# 411_AutoFan_1.net
KiCad netlist of a schematic drawn in EAGLE
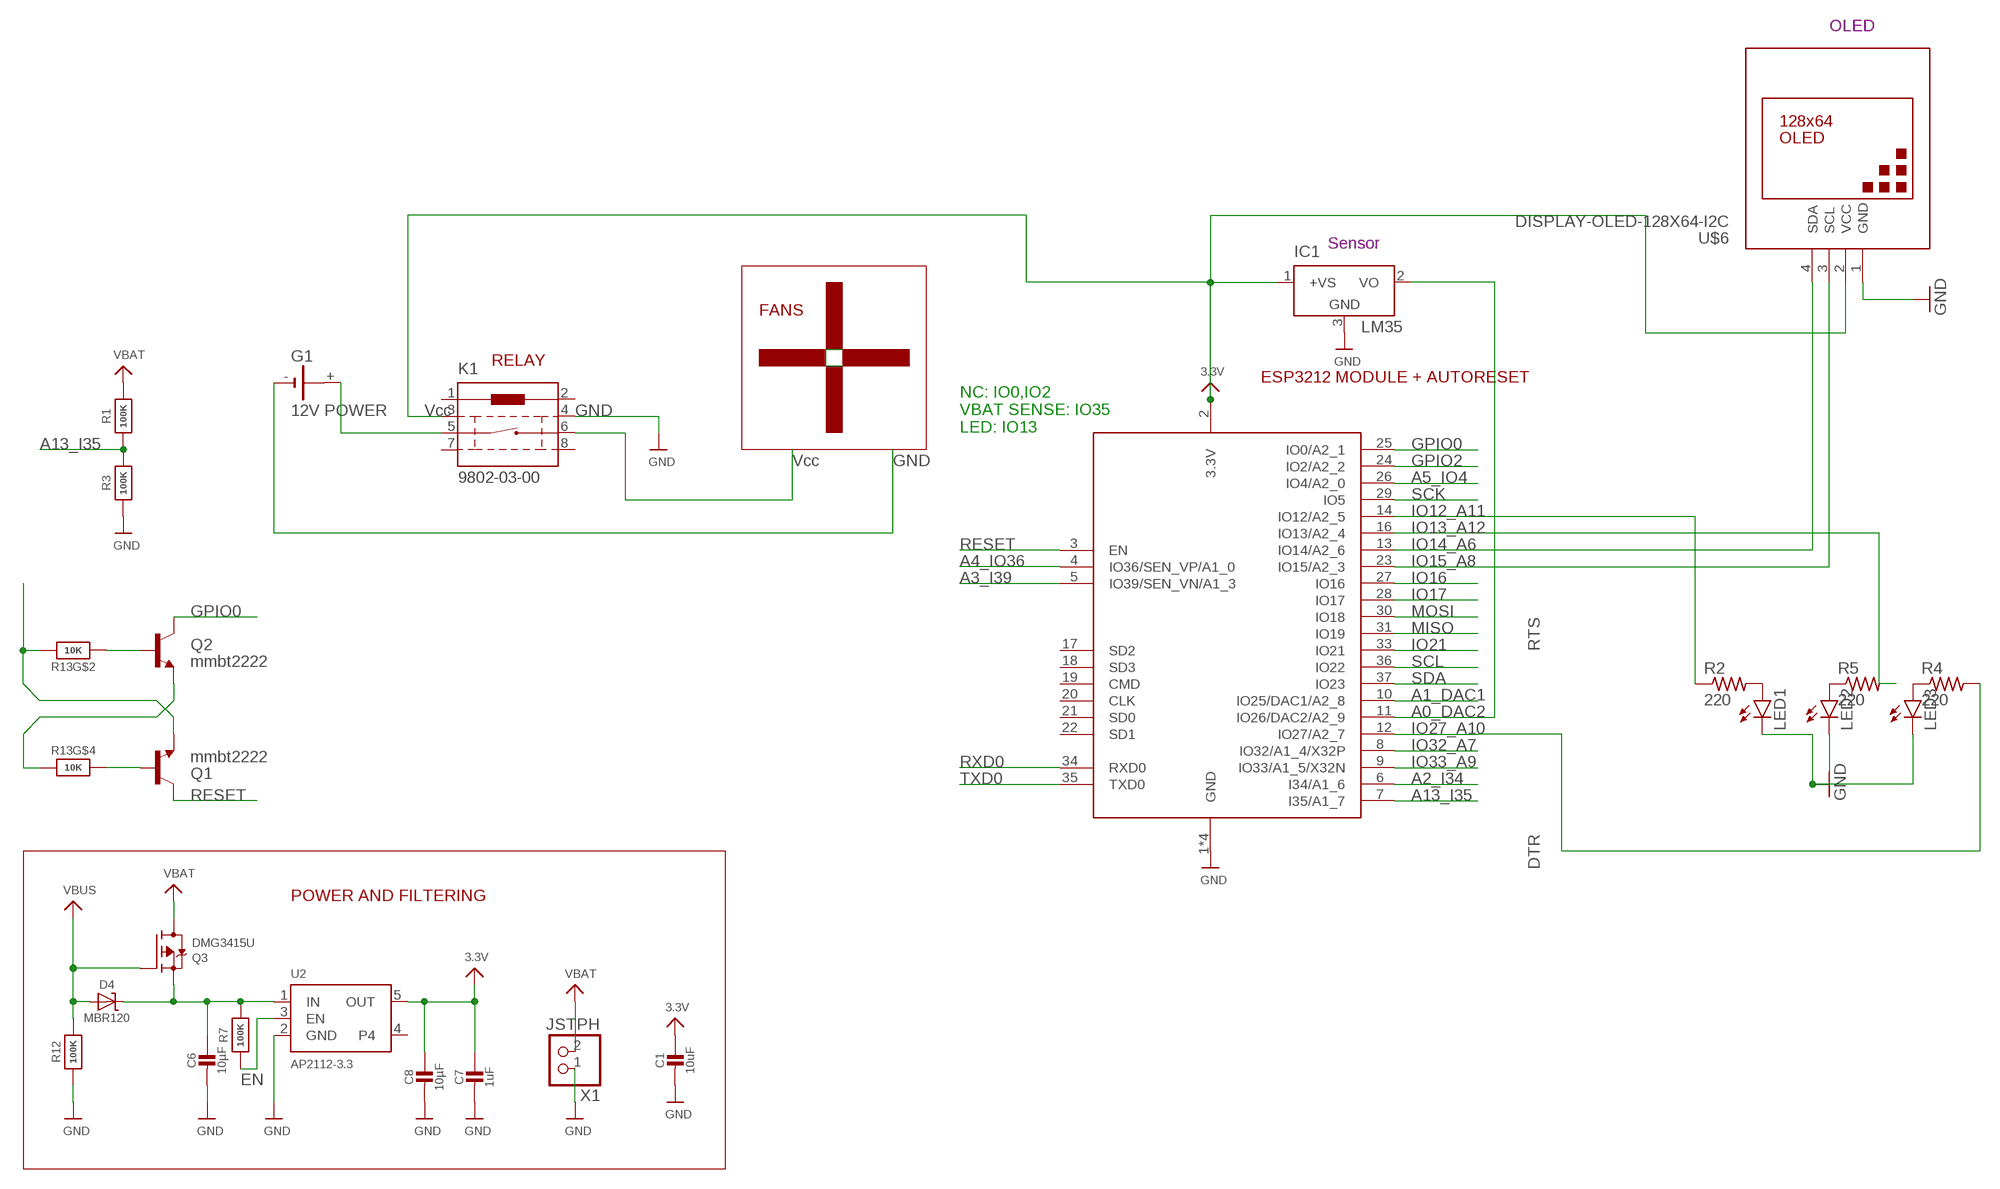
[diagram p0: schematic, sheet 1]

(export (version "E")
  (design (tool "Eeschema 10.0.6"))
  (components
    (comp (ref "C1")
      (value "10uF")
      (footprint "eagle-import:0805-NO")
      (libsource (lib "eagle-import") (part "CAP_CERAMIC0805-NOOUTLINE"))
    )
    (comp (ref "C6")
      (value "10µF")
      (footprint "eagle-import:0805-NO")
      (libsource (lib "eagle-import") (part "CAP_CERAMIC0805-NOOUTLINE"))
    )
    (comp (ref "C7")
      (value "1uF")
      (footprint "eagle-import:0603-NO")
      (libsource (lib "eagle-import") (part "CAP_CERAMIC0603_NO"))
    )
    (comp (ref "C8")
      (value "10µF")
      (footprint "eagle-import:0805-NO")
      (libsource (lib "eagle-import") (part "CAP_CERAMIC0805-NOOUTLINE"))
    )
    (comp (ref "D4")
      (value "MBR120")
      (footprint "eagle-import:SOD-123")
      (libsource (lib "eagle-import") (part "DIODE-SCHOTTKYSOD-123"))
    )
    (comp (ref "G1")
      (value "CR2032V")
      (footprint "eagle-import:CR2032V")
      (libsource (lib "eagle-import") (part "CR2032V"))
    )
    (comp (ref "IC1")
      (value "LM50")
      (footprint "eagle-import:SOT23")
      (libsource (lib "eagle-import") (part "LM50"))
    )
    (comp (ref "K1")
      (value "9802-03-00")
      (footprint "eagle-import:9802-00")
      (libsource (lib "eagle-import") (part "9802-00-03"))
    )
    (comp (ref "LED1")
      (value "LED5MM")
      (footprint "eagle-import:LED5MM")
      (libsource (lib "eagle-import") (part "LED5MM"))
    )
    (comp (ref "LED2")
      (value "LED5MM")
      (footprint "eagle-import:LED5MM")
      (libsource (lib "eagle-import") (part "LED5MM"))
    )
    (comp (ref "LED3")
      (value "LED5MM")
      (footprint "eagle-import:LED5MM")
      (libsource (lib "eagle-import") (part "LED5MM"))
    )
    (comp (ref "Q1")
      (value "mmbt2222")
      (footprint "eagle-import:SOT23-3")
      (libsource (lib "eagle-import") (part "TRANSISTOR_NPNSOT23-3"))
    )
    (comp (ref "Q2")
      (value "mmbt2222")
      (footprint "eagle-import:SOT23-3")
      (libsource (lib "eagle-import") (part "TRANSISTOR_NPNSOT23-3"))
    )
    (comp (ref "Q3")
      (value "DMG3415U")
      (footprint "eagle-import:SOT23-R")
      (libsource (lib "eagle-import") (part "MOSFET-P"))
    )
    (comp (ref "R1")
      (value "100K")
      (footprint "eagle-import:0603-NO")
      (libsource (lib "eagle-import") (part "RESISTOR_0603_NOOUT"))
    )
    (comp (ref "R2")
      (value "220")
      (footprint "eagle-import:0204_7")
      (libsource (lib "eagle-import") (part "R-US_0204/7"))
    )
    (comp (ref "R3")
      (value "100K")
      (footprint "eagle-import:0603-NO")
      (libsource (lib "eagle-import") (part "RESISTOR_0603_NOOUT"))
    )
    (comp (ref "R4")
      (value "220")
      (footprint "eagle-import:0204_7")
      (libsource (lib "eagle-import") (part "R-US_0204/7"))
    )
    (comp (ref "R5")
      (value "220")
      (footprint "eagle-import:0204_7")
      (libsource (lib "eagle-import") (part "R-US_0204/7"))
    )
    (comp (ref "R7")
      (value "100K")
      (footprint "eagle-import:0603-NO")
      (libsource (lib "eagle-import") (part "RESISTOR_0603_NOOUT"))
    )
    (comp (ref "R12")
      (value "100K")
      (footprint "eagle-import:0603-NO")
      (libsource (lib "eagle-import") (part "RESISTOR_0603_NOOUT"))
    )
    (comp (ref "R13")
      (value "10K")
      (footprint "eagle-import:RESPACK_4X0603")
      (libsource (lib "eagle-import") (part "RESISTOR_4PACK"))
    )
    (comp (ref "U$6")
      (value "DISPLAY-OLED-128X64-I2C")
      (footprint "eagle-import:DISPLAY-OLED-128X64-I2C")
      (libsource (lib "eagle-import") (part "DISPLAY-OLED-128X64-I2C"))
    )
    (comp (ref "U2")
      (value "AP2112-3.3")
      (footprint "eagle-import:SOT23-5")
      (libsource (lib "eagle-import") (part "VREG_SOT23-5"))
    )
    (comp (ref "X1")
      (value "JSTPH")
      (footprint "eagle-import:JSTPH2")
      (libsource (lib "eagle-import") (part "CON_JST_PH_2PIN"))
    )
    (comp (ref "X2")
      (value "ESP32_WROOM32_SKINNY")
      (footprint "eagle-import:WROOM32_SKINNY")
      (libsource (lib "eagle-import") (part "ESP32_WROOM32_SKINNY"))
    )
  )
  (nets
    (net (code "1") (name "/A0_DAC2") (class "Default")
      (node (ref "IC1") (pin "2") (pinfunction "VO_2") (pintype "input"))
      (node (ref "X2") (pin "11") (pinfunction "IO26/DAC2/A2_9_11") (pintype "bidirectional"))
    )
    (net (code "2") (name "/A1_DAC1") (class "Default")
      (node (ref "X2") (pin "10") (pinfunction "IO25/DAC1/A2_8_10") (pintype "bidirectional"))
    )
    (net (code "3") (name "/A2_I34") (class "Default")
      (node (ref "X2") (pin "6") (pinfunction "I34/A1_6_6") (pintype "bidirectional"))
    )
    (net (code "4") (name "/A3_I39") (class "Default")
      (node (ref "X2") (pin "5") (pinfunction "IO39/SEN_VN/A1_3_5") (pintype "passive"))
    )
    (net (code "5") (name "/A4_IO36") (class "Default")
      (node (ref "X2") (pin "4") (pinfunction "IO36/SEN_VP/A1_0_4") (pintype "passive"))
    )
    (net (code "6") (name "/A5_IO4") (class "Default")
      (node (ref "X2") (pin "26") (pinfunction "IO4/A2_0_26") (pintype "bidirectional"))
    )
    (net (code "7") (name "/A13_I35") (class "Default")
      (node (ref "R1") (pin "1") (pinfunction "1_1") (pintype "passive"))
      (node (ref "R3") (pin "2") (pinfunction "2_2") (pintype "passive"))
      (node (ref "X2") (pin "7") (pinfunction "I35/A1_7_7") (pintype "bidirectional"))
    )
    (net (code "8") (name "/DTR") (class "Default")
      (node (ref "Q2") (pin "2") (pinfunction "E_2") (pintype "passive"))
      (node (ref "R13") (pin "4") (pinfunction "1_4") (pintype "passive"))
    )
    (net (code "9") (name "/EN") (class "Default")
      (node (ref "R7") (pin "1") (pinfunction "1_1") (pintype "passive"))
      (node (ref "U2") (pin "3") (pinfunction "EN_3") (pintype "input"))
    )
    (net (code "10") (name "/GPIO0") (class "Default")
      (node (ref "Q2") (pin "3") (pinfunction "C_3") (pintype "passive"))
      (node (ref "X2") (pin "25") (pinfunction "IO0/A2_1_25") (pintype "bidirectional"))
    )
    (net (code "11") (name "/GPIO2") (class "Default")
      (node (ref "X2") (pin "24") (pinfunction "IO2/A2_2_24") (pintype "bidirectional"))
    )
    (net (code "12") (name "/IO12_A11") (class "Default")
      (node (ref "R2") (pin "1") (pinfunction "1_1") (pintype "passive"))
      (node (ref "X2") (pin "14") (pinfunction "IO12/A2_5_14") (pintype "bidirectional"))
    )
    (net (code "13") (name "/IO13_A12") (class "Default")
      (node (ref "R5") (pin "2") (pinfunction "2_2") (pintype "passive"))
      (node (ref "X2") (pin "16") (pinfunction "IO13/A2_4_16") (pintype "bidirectional"))
    )
    (net (code "14") (name "/IO14_A6") (class "Default")
      (node (ref "U$6") (pin "4") (pinfunction "SDA_4") (pintype "bidirectional"))
      (node (ref "X2") (pin "13") (pinfunction "IO14/A2_6_13") (pintype "bidirectional"))
    )
    (net (code "15") (name "/IO15_A8") (class "Default")
      (node (ref "U$6") (pin "3") (pinfunction "SCL_3") (pintype "bidirectional"))
      (node (ref "X2") (pin "23") (pinfunction "IO15/A2_3_23") (pintype "bidirectional"))
    )
    (net (code "16") (name "/IO16") (class "Default")
      (node (ref "X2") (pin "27") (pinfunction "IO16_27") (pintype "bidirectional"))
    )
    (net (code "17") (name "/IO17") (class "Default")
      (node (ref "X2") (pin "28") (pinfunction "IO17_28") (pintype "bidirectional"))
    )
    (net (code "18") (name "/IO21") (class "Default")
      (node (ref "X2") (pin "33") (pinfunction "IO21_33") (pintype "bidirectional"))
    )
    (net (code "19") (name "/IO27_A10") (class "Default")
      (node (ref "R4") (pin "2") (pinfunction "2_2") (pintype "passive"))
      (node (ref "X2") (pin "12") (pinfunction "IO27/A2_7_12") (pintype "bidirectional"))
    )
    (net (code "20") (name "/IO32_A7") (class "Default")
      (node (ref "X2") (pin "8") (pinfunction "IO32/A1_4/X32P_8") (pintype "bidirectional"))
    )
    (net (code "21") (name "/IO33_A9") (class "Default")
      (node (ref "X2") (pin "9") (pinfunction "IO33/A1_5/X32N_9") (pintype "bidirectional"))
    )
    (net (code "22") (name "/MISO") (class "Default")
      (node (ref "X2") (pin "31") (pinfunction "IO19_31") (pintype "bidirectional"))
    )
    (net (code "23") (name "/MOSI") (class "Default")
      (node (ref "X2") (pin "30") (pinfunction "IO18_30") (pintype "bidirectional"))
    )
    (net (code "24") (name "/RESET") (class "Default")
      (node (ref "Q1") (pin "3") (pinfunction "C_3") (pintype "passive"))
      (node (ref "X2") (pin "3") (pinfunction "EN_3") (pintype "input"))
    )
    (net (code "25") (name "/RTS") (class "Default")
      (node (ref "Q1") (pin "2") (pinfunction "E_2") (pintype "passive"))
      (node (ref "R13") (pin "7") (pinfunction "2_7") (pintype "passive"))
    )
    (net (code "26") (name "/RXD0") (class "Default")
      (node (ref "X2") (pin "34") (pinfunction "RXD0_34") (pintype "input"))
    )
    (net (code "27") (name "/SCK") (class "Default")
      (node (ref "X2") (pin "29") (pinfunction "IO5_29") (pintype "bidirectional"))
    )
    (net (code "28") (name "/SCL") (class "Default")
      (node (ref "X2") (pin "36") (pinfunction "IO22_36") (pintype "bidirectional"))
    )
    (net (code "29") (name "/SDA") (class "Default")
      (node (ref "X2") (pin "37") (pinfunction "IO23_37") (pintype "bidirectional"))
    )
    (net (code "30") (name "/TXD0") (class "Default")
      (node (ref "X2") (pin "35") (pinfunction "TXD0_35") (pintype "output"))
    )
    (net (code "31") (name "3.3V") (class "Default")
      (node (ref "C1") (pin "1") (pinfunction "1_1") (pintype "passive"))
      (node (ref "C7") (pin "1") (pinfunction "1_1") (pintype "passive"))
      (node (ref "C8") (pin "1") (pinfunction "1_1") (pintype "passive"))
      (node (ref "IC1") (pin "1") (pinfunction "+VS_1") (pintype "input"))
      (node (ref "K1") (pin "3") (pinfunction "3_3") (pintype "passive"))
      (node (ref "U$6") (pin "2") (pinfunction "VCC_2") (pintype "power_in"))
      (node (ref "U2") (pin "5") (pinfunction "OUT_5") (pintype "power_in"))
      (node (ref "X2") (pin "2") (pinfunction "3.3V_2") (pintype "passive"))
    )
    (net (code "32") (name "GND") (class "Default")
      (node (ref "C1") (pin "2") (pinfunction "2_2") (pintype "passive"))
      (node (ref "C6") (pin "2") (pinfunction "2_2") (pintype "passive"))
      (node (ref "C7") (pin "2") (pinfunction "2_2") (pintype "passive"))
      (node (ref "C8") (pin "2") (pinfunction "2_2") (pintype "passive"))
      (node (ref "IC1") (pin "3") (pinfunction "GND_3") (pintype "power_in"))
      (node (ref "K1") (pin "4") (pinfunction "4_4") (pintype "passive"))
      (node (ref "LED1") (pin "K") (pinfunction "C_K") (pintype "passive"))
      (node (ref "LED2") (pin "K") (pinfunction "C_K") (pintype "passive"))
      (node (ref "LED3") (pin "K") (pinfunction "C_K") (pintype "passive"))
      (node (ref "R12") (pin "1") (pinfunction "1_1") (pintype "passive"))
      (node (ref "R3") (pin "1") (pinfunction "1_1") (pintype "passive"))
      (node (ref "U$6") (pin "1") (pinfunction "GND_1") (pintype "power_in"))
      (node (ref "U2") (pin "2") (pinfunction "GND_2") (pintype "power_in"))
      (node (ref "X1") (pin "1") (pinfunction "1_1") (pintype "passive"))
      (node (ref "X2") (pin "1") (pinfunction "GND_1") (pintype "passive"))
      (node (ref "X2") (pin "15") (pinfunction "GND_15") (pintype "passive"))
      (node (ref "X2") (pin "38") (pinfunction "GND_38") (pintype "passive"))
      (node (ref "X2") (pin "P$1") (pinfunction "GND_P$1") (pintype "passive"))
    )
    (net (code "33") (name "Net-(G1-Pad+)") (class "Default")
      (node (ref "G1") (pin "+") (pinfunction "+_+") (pintype "passive"))
      (node (ref "K1") (pin "5") (pinfunction "5_5") (pintype "passive"))
    )
    (net (code "34") (name "Net-(LED1-PadA)") (class "Default")
      (node (ref "LED1") (pin "A") (pinfunction "A_A") (pintype "passive"))
      (node (ref "R2") (pin "2") (pinfunction "2_2") (pintype "passive"))
    )
    (net (code "35") (name "Net-(LED2-PadA)") (class "Default")
      (node (ref "LED2") (pin "A") (pinfunction "A_A") (pintype "passive"))
      (node (ref "R5") (pin "1") (pinfunction "1_1") (pintype "passive"))
    )
    (net (code "36") (name "Net-(LED3-PadA)") (class "Default")
      (node (ref "LED3") (pin "A") (pinfunction "A_A") (pintype "passive"))
      (node (ref "R4") (pin "1") (pinfunction "1_1") (pintype "passive"))
    )
    (net (code "37") (name "Net-(Q1-B)") (class "Default")
      (node (ref "Q1") (pin "1") (pinfunction "B_1") (pintype "passive"))
      (node (ref "R13") (pin "5") (pinfunction "2_5") (pintype "passive"))
    )
    (net (code "38") (name "Net-(Q2-B)") (class "Default")
      (node (ref "Q2") (pin "1") (pinfunction "B_1") (pintype "passive"))
      (node (ref "R13") (pin "2") (pinfunction "1_2") (pintype "passive"))
    )
    (net (code "39") (name "Net-(Q3-S)") (class "Default")
      (node (ref "C6") (pin "1") (pinfunction "1_1") (pintype "passive"))
      (node (ref "D4") (pin "C") (pinfunction "C_C") (pintype "passive"))
      (node (ref "Q3") (pin "2") (pinfunction "S_2") (pintype "passive"))
      (node (ref "R7") (pin "2") (pinfunction "2_2") (pintype "passive"))
      (node (ref "U2") (pin "1") (pinfunction "IN_1") (pintype "power_in"))
    )
    (net (code "40") (name "VBAT") (class "Default")
      (node (ref "Q3") (pin "3") (pinfunction "D_3") (pintype "passive"))
      (node (ref "R1") (pin "2") (pinfunction "2_2") (pintype "passive"))
      (node (ref "X1") (pin "2") (pinfunction "2_2") (pintype "passive"))
    )
    (net (code "41") (name "VBUS") (class "Default")
      (node (ref "D4") (pin "A") (pinfunction "A_A") (pintype "passive"))
      (node (ref "Q3") (pin "1") (pinfunction "G_1") (pintype "passive"))
      (node (ref "R12") (pin "2") (pinfunction "2_2") (pintype "passive"))
    )
    (net (code "42") (name "unconnected-(G1-+-Pad+@1)") (class "Default")
      (node (ref "G1") (pin "+@1") (pinfunction "+_+@1") (pintype "passive"))
    )
    (net (code "43") (name "unconnected-(G1-Pad-)") (class "Default")
      (node (ref "G1") (pin "-") (pinfunction "-_-") (pintype "passive"))
    )
    (net (code "44") (name "unconnected-(K1-Pad1)") (class "Default")
      (node (ref "K1") (pin "1") (pinfunction "1_1") (pintype "passive"))
    )
    (net (code "45") (name "unconnected-(K1-Pad2)") (class "Default")
      (node (ref "K1") (pin "2") (pinfunction "2_2") (pintype "passive"))
    )
    (net (code "46") (name "unconnected-(K1-Pad6)") (class "Default")
      (node (ref "K1") (pin "6") (pinfunction "6_6") (pintype "passive"))
    )
    (net (code "47") (name "unconnected-(K1-Pad7)") (class "Default")
      (node (ref "K1") (pin "7") (pinfunction "7_7") (pintype "passive"))
    )
    (net (code "48") (name "unconnected-(K1-Pad8)") (class "Default")
      (node (ref "K1") (pin "8") (pinfunction "8_8") (pintype "passive"))
    )
    (net (code "49") (name "unconnected-(U2-P4-Pad4)") (class "Default")
      (node (ref "U2") (pin "4") (pinfunction "P4_4") (pintype "bidirectional"))
    )
    (net (code "50") (name "unconnected-(X2-CLK-Pad20)") (class "Default")
      (node (ref "X2") (pin "20") (pinfunction "CLK_20") (pintype "bidirectional"))
    )
    (net (code "51") (name "unconnected-(X2-CMD-Pad19)") (class "Default")
      (node (ref "X2") (pin "19") (pinfunction "CMD_19") (pintype "bidirectional"))
    )
    (net (code "52") (name "unconnected-(X2-SD0-Pad21)") (class "Default")
      (node (ref "X2") (pin "21") (pinfunction "SD0_21") (pintype "bidirectional"))
    )
    (net (code "53") (name "unconnected-(X2-SD1-Pad22)") (class "Default")
      (node (ref "X2") (pin "22") (pinfunction "SD1_22") (pintype "bidirectional"))
    )
    (net (code "54") (name "unconnected-(X2-SD2-Pad17)") (class "Default")
      (node (ref "X2") (pin "17") (pinfunction "SD2_17") (pintype "bidirectional"))
    )
    (net (code "55") (name "unconnected-(X2-SD3-Pad18)") (class "Default")
      (node (ref "X2") (pin "18") (pinfunction "SD3_18") (pintype "bidirectional"))
    )
  )
)
